# samd5x5.net
KiCad netlist of a schematic drawn in EAGLE
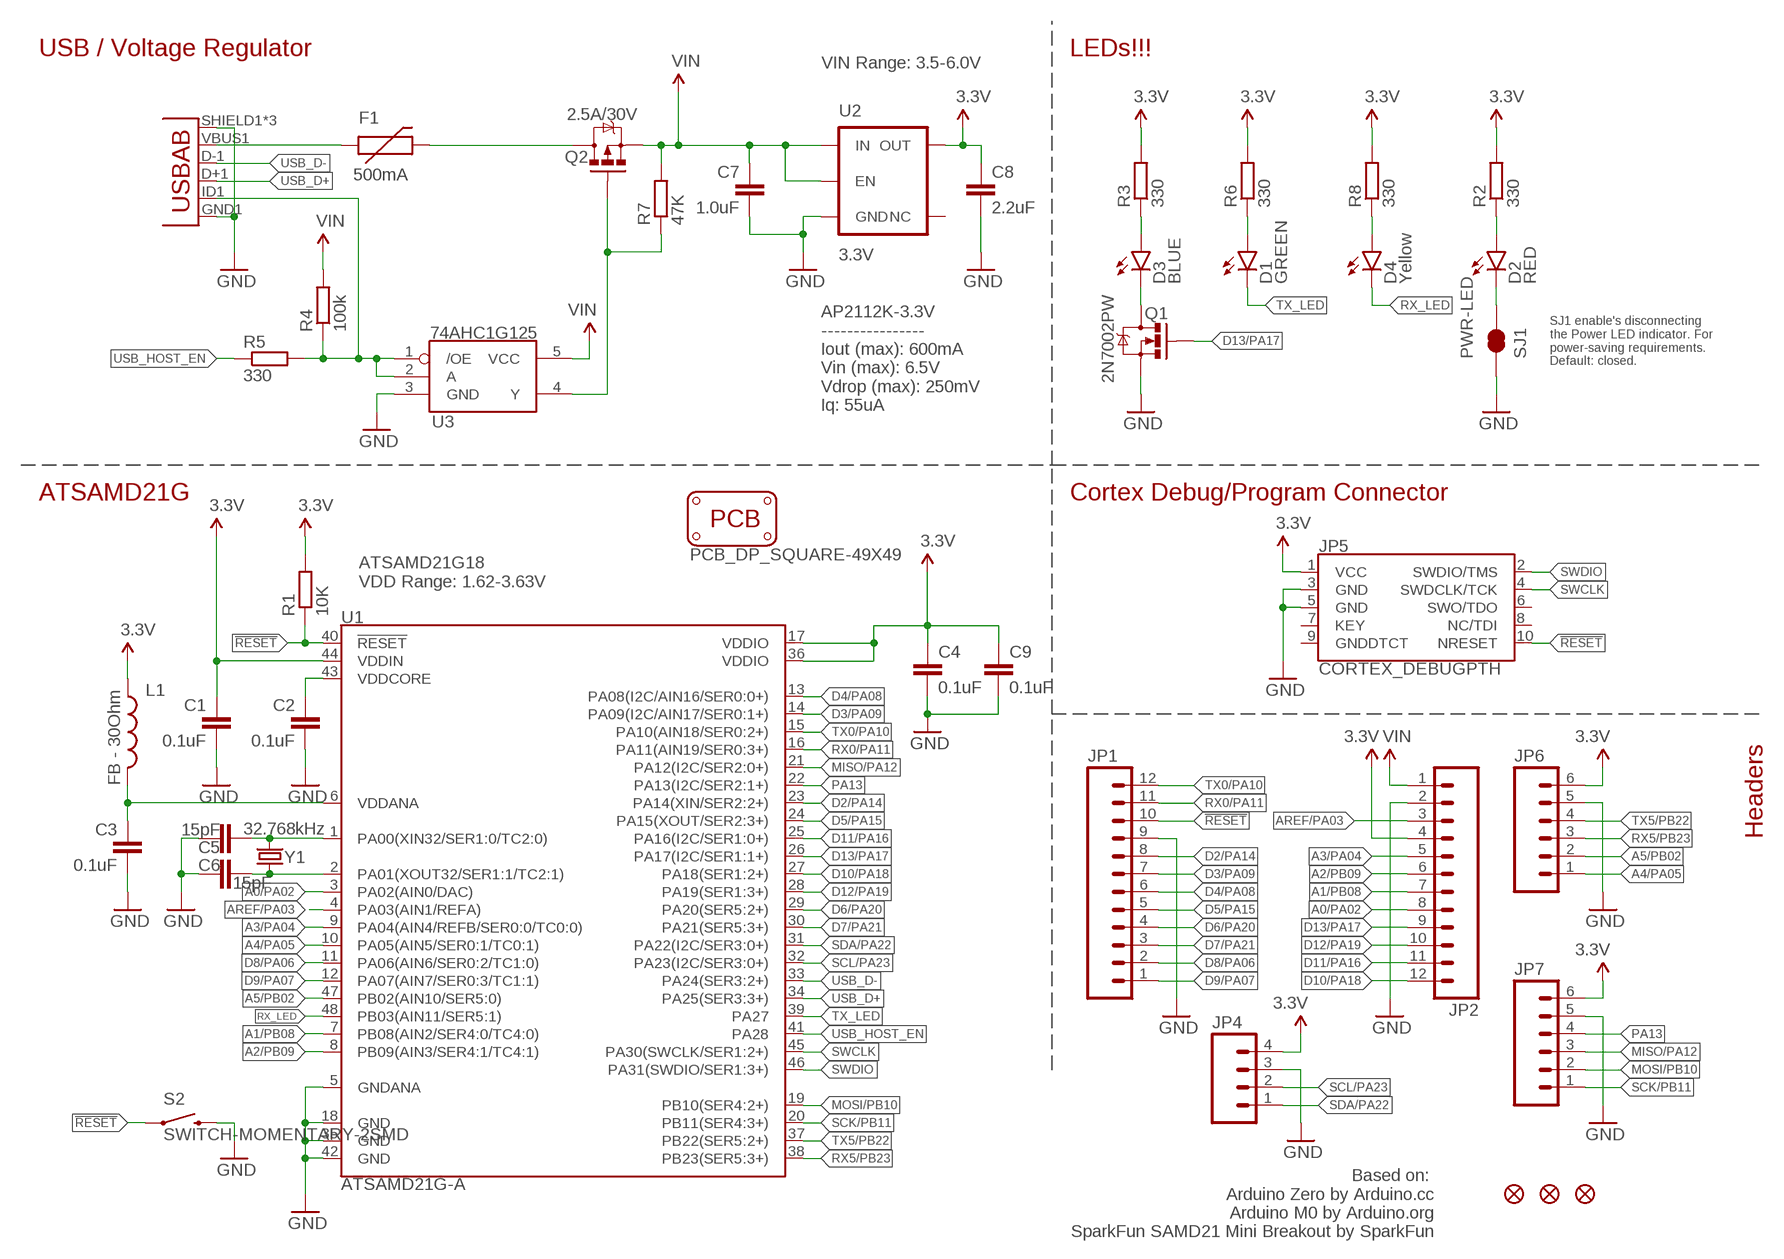
[diagram p0: schematic, sheet 1]

(export (version "E")
  (design (tool "Eeschema 10.0.6"))
  (components
    (comp (ref "C1")
      (value "0.1uF")
      (footprint "eagle-import:0402-CAP")
      (libsource (lib "eagle-import") (part "0.1UF-16V(+-10%)(0402)"))
    )
    (comp (ref "C2")
      (value "0.1uF")
      (footprint "eagle-import:0402-CAP")
      (libsource (lib "eagle-import") (part "0.1UF-16V(+-10%)(0402)"))
    )
    (comp (ref "C3")
      (value "0.1uF")
      (footprint "eagle-import:0402-CAP")
      (libsource (lib "eagle-import") (part "0.1UF-16V(+-10%)(0402)"))
    )
    (comp (ref "C4")
      (value "0.1uF")
      (footprint "eagle-import:0402-CAP")
      (libsource (lib "eagle-import") (part "0.1UF-16V(+-10%)(0402)"))
    )
    (comp (ref "C5")
      (value "15pF")
      (footprint "eagle-import:0402-CAP")
      (libsource (lib "eagle-import") (part "15PF-50V(+-5%)(0402)"))
    )
    (comp (ref "C6")
      (value "15pF")
      (footprint "eagle-import:0402-CAP")
      (libsource (lib "eagle-import") (part "15PF-50V(+-5%)(0402)"))
    )
    (comp (ref "C7")
      (value "1.0uF")
      (footprint "eagle-import:C0603K")
      (libsource (lib "eagle-import") (part "C-EUC0603K"))
    )
    (comp (ref "C8")
      (value "2.2uF")
      (footprint "eagle-import:0603-CAP")
      (libsource (lib "eagle-import") (part "2.2UF-10V-20%(0603)"))
    )
    (comp (ref "C9")
      (value "0.1uF")
      (footprint "eagle-import:0402-CAP")
      (libsource (lib "eagle-import") (part "0.1UF-16V(+-10%)(0402)"))
    )
    (comp (ref "D1")
      (value "GREEN")
      (footprint "eagle-import:LED-0603")
      (libsource (lib "eagle-import") (part "LED-GREEN0603"))
    )
    (comp (ref "D2")
      (value "RED")
      (footprint "eagle-import:LED-0603")
      (libsource (lib "eagle-import") (part "LED-RED0603"))
    )
    (comp (ref "D3")
      (value "BLUE")
      (footprint "eagle-import:LED-0603")
      (libsource (lib "eagle-import") (part "LED-BLUE0603"))
    )
    (comp (ref "D4")
      (value "Yellow")
      (footprint "eagle-import:LED-0603")
      (libsource (lib "eagle-import") (part "LED-YELLOW0603"))
    )
    (comp (ref "F1")
      (value "500mA")
      (footprint "eagle-import:PTC-1206")
      (libsource (lib "eagle-import") (part "PTCSMD"))
    )
    (comp (ref "FID1")
      (value "FIDUCIAL1X2")
      (footprint "eagle-import:FIDUCIAL-1X2")
      (libsource (lib "eagle-import") (part "FIDUCIAL1X2"))
    )
    (comp (ref "FID2")
      (value "FIDUCIAL1X2")
      (footprint "eagle-import:FIDUCIAL-1X2")
      (libsource (lib "eagle-import") (part "FIDUCIAL1X2"))
    )
    (comp (ref "FID3")
      (value "FIDUCIAL1X2")
      (footprint "eagle-import:FIDUCIAL-1X2")
      (libsource (lib "eagle-import") (part "FIDUCIAL1X2"))
    )
    (comp (ref "JP1")
      (value "M12NO_SILK")
      (footprint "eagle-import:1X12_NO_SILK")
      (libsource (lib "eagle-import") (part "M12NO_SILK"))
    )
    (comp (ref "JP2")
      (value "M12NO_SILK")
      (footprint "eagle-import:1X12_NO_SILK")
      (libsource (lib "eagle-import") (part "M12NO_SILK"))
    )
    (comp (ref "JP3")
      (value "USB-ABCONN-11794")
      (footprint "eagle-import:USB-AB-MICRO-SMD_V03")
      (libsource (lib "eagle-import") (part "USB-ABCONN-11794"))
    )
    (comp (ref "JP4")
      (value "M041X04_NO_SILK")
      (footprint "eagle-import:1X04_NO_SILK")
      (libsource (lib "eagle-import") (part "M041X04_NO_SILK"))
    )
    (comp (ref "JP5")
      (value "CORTEX_DEBUGPTH")
      (footprint "eagle-import:2X5-PTH-1.27MM")
      (libsource (lib "eagle-import") (part "CORTEX_DEBUGPTH"))
    )
    (comp (ref "JP6")
      (value "M06NO_SILK_FEMALE_PTH")
      (footprint "eagle-import:1X06_NO_SILK")
      (libsource (lib "eagle-import") (part "M06NO_SILK_FEMALE_PTH"))
    )
    (comp (ref "JP7")
      (value "M06NO_SILK_FEMALE_PTH")
      (footprint "eagle-import:1X06_NO_SILK")
      (libsource (lib "eagle-import") (part "M06NO_SILK_FEMALE_PTH"))
    )
    (comp (ref "L1")
      (value "FB - 30Ohm")
      (footprint "eagle-import:0603")
      (libsource (lib "eagle-import") (part "INDUCTOR0603"))
    )
    (comp (ref "PCB1")
      (value "PCB_DP_SQUARE-49X49")
      (footprint "eagle-import:DP4949V1")
      (libsource (lib "eagle-import") (part "PCB_DP_SQUARE-49X49"))
    )
    (comp (ref "Q1")
      (value "2N7002PW")
      (footprint "eagle-import:SOT323")
      (libsource (lib "eagle-import") (part "MOSFET-NCHANNEL2N7002PW"))
    )
    (comp (ref "Q2")
      (value "2.5A/30V")
      (footprint "eagle-import:SOT23-3")
      (libsource (lib "eagle-import") (part "MOSFET-PCHANNELDMG2307L"))
    )
    (comp (ref "R1")
      (value "10K")
      (footprint "eagle-import:R0402")
      (libsource (lib "eagle-import") (part "R-EU_R0402"))
    )
    (comp (ref "R2")
      (value "330")
      (footprint "eagle-import:R0402")
      (libsource (lib "eagle-import") (part "R-EU_R0402"))
    )
    (comp (ref "R3")
      (value "330")
      (footprint "eagle-import:R0402")
      (libsource (lib "eagle-import") (part "R-EU_R0402"))
    )
    (comp (ref "R4")
      (value "100k")
      (footprint "eagle-import:R0402")
      (libsource (lib "eagle-import") (part "R-EU_R0402"))
    )
    (comp (ref "R5")
      (value "330")
      (footprint "eagle-import:R0402")
      (libsource (lib "eagle-import") (part "R-EU_R0402"))
    )
    (comp (ref "R6")
      (value "330")
      (footprint "eagle-import:R0402")
      (libsource (lib "eagle-import") (part "R-EU_R0402"))
    )
    (comp (ref "R7")
      (value "47K")
      (footprint "eagle-import:R0402")
      (libsource (lib "eagle-import") (part "R-EU_R0402"))
    )
    (comp (ref "R8")
      (value "330")
      (footprint "eagle-import:R0402")
      (libsource (lib "eagle-import") (part "R-EU_R0402"))
    )
    (comp (ref "S2")
      (value "SWITCH-MOMENTARY-2SMD")
      (footprint "eagle-import:TACTILE-SWITCH-SMD")
      (libsource (lib "eagle-import") (part "SWITCH-MOMENTARY-2SMD"))
    )
    (comp (ref "SJ1")
      (value "PWR-LED")
      (footprint "eagle-import:PAD-JUMPER-2-NC_BY_TRACE_NO_SILK")
      (libsource (lib "eagle-import") (part "JUMPER-PAD-2-NC_BY_TRACENO_SILK"))
    )
    (comp (ref "U1")
      (value "ATSAMD21G-A")
      (footprint "eagle-import:TQFP-48")
      (libsource (lib "eagle-import") (part "ATSAMD21G-A"))
    )
    (comp (ref "U2")
      (value "3.3V")
      (footprint "eagle-import:SOT23-5")
      (libsource (lib "eagle-import") (part "V_REG_AP2112K-3.3V"))
    )
    (comp (ref "U3")
      (value "74AHC1G125")
      (footprint "eagle-import:SOT23-5")
      (libsource (lib "eagle-import") (part "74AHC1G125"))
    )
    (comp (ref "Y1")
      (value "32.768kHz")
      (footprint "eagle-import:CRYSTAL-SMD-3.2X1.5MM")
      (libsource (lib "eagle-import") (part "CRYSTAL3.2X1.5MM"))
    )
  )
  (nets
    (net (code "1") (name "/~{RESET}") (class "Default")
      (node (ref "JP1") (pin "10") (pinfunction "10_10") (pintype "passive"))
      (node (ref "JP5") (pin "10") (pinfunction "NRESET_10") (pintype "bidirectional"))
      (node (ref "R1") (pin "1") (pinfunction "1_1") (pintype "passive"))
      (node (ref "S2") (pin "1") (pinfunction "1_1") (pintype "passive"))
      (node (ref "U1") (pin "40") (pinfunction "~{RESET}_40") (pintype "bidirectional"))
    )
    (net (code "2") (name "3.3V") (class "Default")
      (node (ref "C1") (pin "1") (pinfunction "1_1") (pintype "passive"))
      (node (ref "C4") (pin "1") (pinfunction "1_1") (pintype "passive"))
      (node (ref "C8") (pin "1") (pinfunction "1_1") (pintype "passive"))
      (node (ref "C9") (pin "1") (pinfunction "1_1") (pintype "passive"))
      (node (ref "JP2") (pin "4") (pinfunction "4_4") (pintype "passive"))
      (node (ref "JP4") (pin "4") (pinfunction "4_4") (pintype "passive"))
      (node (ref "JP5") (pin "1") (pinfunction "VCC_1") (pintype "bidirectional"))
      (node (ref "JP6") (pin "6") (pinfunction "6_6") (pintype "passive"))
      (node (ref "JP7") (pin "6") (pinfunction "6_6") (pintype "passive"))
      (node (ref "L1") (pin "1") (pinfunction "1_1") (pintype "passive"))
      (node (ref "R1") (pin "2") (pinfunction "2_2") (pintype "passive"))
      (node (ref "R2") (pin "2") (pinfunction "2_2") (pintype "passive"))
      (node (ref "R3") (pin "2") (pinfunction "2_2") (pintype "passive"))
      (node (ref "R6") (pin "2") (pinfunction "2_2") (pintype "passive"))
      (node (ref "R8") (pin "2") (pinfunction "2_2") (pintype "passive"))
      (node (ref "U1") (pin "17") (pinfunction "VDDIO_17") (pintype "bidirectional"))
      (node (ref "U1") (pin "36") (pinfunction "VDDIO_36") (pintype "bidirectional"))
      (node (ref "U1") (pin "44") (pinfunction "VDDIN_44") (pintype "bidirectional"))
      (node (ref "U2") (pin "5") (pinfunction "OUT_5") (pintype "passive"))
    )
    (net (code "3") (name "A0{slash}PA02") (class "Default")
      (node (ref "JP2") (pin "8") (pinfunction "8_8") (pintype "passive"))
      (node (ref "U1") (pin "3") (pinfunction "PA02(AIN0/DAC)_3") (pintype "bidirectional"))
    )
    (net (code "4") (name "A1{slash}PB08") (class "Default")
      (node (ref "JP2") (pin "7") (pinfunction "7_7") (pintype "passive"))
      (node (ref "U1") (pin "7") (pinfunction "PB08(AIN2/SER4:0/TC4:0)_7") (pintype "bidirectional"))
    )
    (net (code "5") (name "A2{slash}PB09") (class "Default")
      (node (ref "JP2") (pin "6") (pinfunction "6_6") (pintype "passive"))
      (node (ref "U1") (pin "8") (pinfunction "PB09(AIN3/SER4:1/TC4:1)_8") (pintype "bidirectional"))
    )
    (net (code "6") (name "A3{slash}PA04") (class "Default")
      (node (ref "JP2") (pin "5") (pinfunction "5_5") (pintype "passive"))
      (node (ref "U1") (pin "9") (pinfunction "PA04(AIN4/REFB/SER0:0/TC0:0)_9") (pintype "bidirectional"))
    )
    (net (code "7") (name "A4{slash}PA05") (class "Default")
      (node (ref "JP6") (pin "1") (pinfunction "1_1") (pintype "passive"))
      (node (ref "U1") (pin "10") (pinfunction "PA05(AIN5/SER0:1/TC0:1)_10") (pintype "bidirectional"))
    )
    (net (code "8") (name "A5{slash}PB02") (class "Default")
      (node (ref "JP6") (pin "2") (pinfunction "2_2") (pintype "passive"))
      (node (ref "U1") (pin "47") (pinfunction "PB02(AIN10/SER5:0)_47") (pintype "bidirectional"))
    )
    (net (code "9") (name "AREF{slash}PA03") (class "Default")
      (node (ref "JP2") (pin "3") (pinfunction "3_3") (pintype "passive"))
      (node (ref "U1") (pin "4") (pinfunction "PA03(AIN1/REFA)_4") (pintype "bidirectional"))
    )
    (net (code "10") (name "D2{slash}PA14") (class "Default")
      (node (ref "JP1") (pin "8") (pinfunction "8_8") (pintype "passive"))
      (node (ref "U1") (pin "23") (pinfunction "PA14(XIN/SER2:2+)_23") (pintype "bidirectional"))
    )
    (net (code "11") (name "D3{slash}PA09") (class "Default")
      (node (ref "JP1") (pin "7") (pinfunction "7_7") (pintype "passive"))
      (node (ref "U1") (pin "14") (pinfunction "PA09(I2C/AIN17/SER0:1+)_14") (pintype "bidirectional"))
    )
    (net (code "12") (name "D4{slash}PA08") (class "Default")
      (node (ref "JP1") (pin "6") (pinfunction "6_6") (pintype "passive"))
      (node (ref "U1") (pin "13") (pinfunction "PA08(I2C/AIN16/SER0:0+)_13") (pintype "bidirectional"))
    )
    (net (code "13") (name "D5{slash}PA15") (class "Default")
      (node (ref "JP1") (pin "5") (pinfunction "5_5") (pintype "passive"))
      (node (ref "U1") (pin "24") (pinfunction "PA15(XOUT/SER2:3+)_24") (pintype "bidirectional"))
    )
    (net (code "14") (name "D6{slash}PA20") (class "Default")
      (node (ref "JP1") (pin "4") (pinfunction "4_4") (pintype "passive"))
      (node (ref "U1") (pin "29") (pinfunction "PA20(SER5:2+)_29") (pintype "bidirectional"))
    )
    (net (code "15") (name "D7{slash}PA21") (class "Default")
      (node (ref "JP1") (pin "3") (pinfunction "3_3") (pintype "passive"))
      (node (ref "U1") (pin "30") (pinfunction "PA21(SER5:3+)_30") (pintype "bidirectional"))
    )
    (net (code "16") (name "D8{slash}PA06") (class "Default")
      (node (ref "JP1") (pin "2") (pinfunction "2_2") (pintype "passive"))
      (node (ref "U1") (pin "11") (pinfunction "PA06(AIN6/SER0:2/TC1:0)_11") (pintype "bidirectional"))
    )
    (net (code "17") (name "D9{slash}PA07") (class "Default")
      (node (ref "JP1") (pin "1") (pinfunction "1_1") (pintype "passive"))
      (node (ref "U1") (pin "12") (pinfunction "PA07(AIN7/SER0:3/TC1:1)_12") (pintype "bidirectional"))
    )
    (net (code "18") (name "D10{slash}PA18") (class "Default")
      (node (ref "JP2") (pin "12") (pinfunction "12_12") (pintype "passive"))
      (node (ref "U1") (pin "27") (pinfunction "PA18(SER1:2+)_27") (pintype "bidirectional"))
    )
    (net (code "19") (name "D11{slash}PA16") (class "Default")
      (node (ref "JP2") (pin "11") (pinfunction "11_11") (pintype "passive"))
      (node (ref "U1") (pin "25") (pinfunction "PA16(I2C/SER1:0+)_25") (pintype "bidirectional"))
    )
    (net (code "20") (name "D12{slash}PA19") (class "Default")
      (node (ref "JP2") (pin "10") (pinfunction "10_10") (pintype "passive"))
      (node (ref "U1") (pin "28") (pinfunction "PA19(SER1:3+)_28") (pintype "bidirectional"))
    )
    (net (code "21") (name "D13{slash}PA17") (class "Default")
      (node (ref "JP2") (pin "9") (pinfunction "9_9") (pintype "passive"))
      (node (ref "Q1") (pin "1") (pinfunction "G_1") (pintype "passive"))
      (node (ref "U1") (pin "26") (pinfunction "PA17(I2C/SER1:1+)_26") (pintype "bidirectional"))
    )
    (net (code "22") (name "GND") (class "Default")
      (node (ref "C1") (pin "2") (pinfunction "2_2") (pintype "passive"))
      (node (ref "C2") (pin "2") (pinfunction "2_2") (pintype "passive"))
      (node (ref "C3") (pin "2") (pinfunction "2_2") (pintype "passive"))
      (node (ref "C4") (pin "2") (pinfunction "2_2") (pintype "passive"))
      (node (ref "C5") (pin "1") (pinfunction "1_1") (pintype "passive"))
      (node (ref "C6") (pin "2") (pinfunction "2_2") (pintype "passive"))
      (node (ref "C7") (pin "2") (pinfunction "2_2") (pintype "passive"))
      (node (ref "C8") (pin "2") (pinfunction "2_2") (pintype "passive"))
      (node (ref "C9") (pin "2") (pinfunction "2_2") (pintype "passive"))
      (node (ref "JP1") (pin "9") (pinfunction "9_9") (pintype "passive"))
      (node (ref "JP2") (pin "2") (pinfunction "2_2") (pintype "passive"))
      (node (ref "JP3") (pin "GND1") (pinfunction "GND_GND1") (pintype "bidirectional"))
      (node (ref "JP3") (pin "SHIELD1") (pinfunction "SHIELD_SHIELD1") (pintype "bidirectional"))
      (node (ref "JP3") (pin "SHIELD2") (pinfunction "SHIELD_SHIELD2") (pintype "bidirectional"))
      (node (ref "JP3") (pin "SHIELD3") (pinfunction "SHIELD_SHIELD3") (pintype "bidirectional"))
      (node (ref "JP4") (pin "3") (pinfunction "3_3") (pintype "passive"))
      (node (ref "JP5") (pin "3") (pinfunction "GND_3") (pintype "bidirectional"))
      (node (ref "JP5") (pin "5") (pinfunction "GND_5") (pintype "bidirectional"))
      (node (ref "JP6") (pin "5") (pinfunction "5_5") (pintype "passive"))
      (node (ref "JP7") (pin "5") (pinfunction "5_5") (pintype "passive"))
      (node (ref "Q1") (pin "2") (pinfunction "S_2") (pintype "passive"))
      (node (ref "S2") (pin "3") (pinfunction "2_3") (pintype "passive"))
      (node (ref "SJ1") (pin "1") (pinfunction "1_1") (pintype "passive"))
      (node (ref "U1") (pin "18") (pinfunction "GND_18") (pintype "bidirectional"))
      (node (ref "U1") (pin "35") (pinfunction "GND_35") (pintype "bidirectional"))
      (node (ref "U1") (pin "42") (pinfunction "GND_42") (pintype "bidirectional"))
      (node (ref "U1") (pin "5") (pinfunction "GNDANA_5") (pintype "bidirectional"))
      (node (ref "U2") (pin "2") (pinfunction "GND_2") (pintype "input"))
      (node (ref "U3") (pin "3") (pinfunction "GND_3") (pintype "bidirectional"))
    )
    (net (code "23") (name "MISO{slash}PA12") (class "Default")
      (node (ref "JP7") (pin "3") (pinfunction "3_3") (pintype "passive"))
      (node (ref "U1") (pin "21") (pinfunction "PA12(I2C/SER2:0+)_21") (pintype "bidirectional"))
    )
    (net (code "24") (name "MOSI{slash}PB10") (class "Default")
      (node (ref "JP7") (pin "2") (pinfunction "2_2") (pintype "passive"))
      (node (ref "U1") (pin "19") (pinfunction "PB10(SER4:2+)_19") (pintype "bidirectional"))
    )
    (net (code "25") (name "Net-(D1-PadA)") (class "Default")
      (node (ref "D1") (pin "A") (pinfunction "A_A") (pintype "passive"))
      (node (ref "R6") (pin "1") (pinfunction "1_1") (pintype "passive"))
    )
    (net (code "26") (name "Net-(D2-PadA)") (class "Default")
      (node (ref "D2") (pin "A") (pinfunction "A_A") (pintype "passive"))
      (node (ref "R2") (pin "1") (pinfunction "1_1") (pintype "passive"))
    )
    (net (code "27") (name "Net-(D2-PadC)") (class "Default")
      (node (ref "D2") (pin "C") (pinfunction "C_C") (pintype "passive"))
      (node (ref "SJ1") (pin "2") (pinfunction "2_2") (pintype "passive"))
    )
    (net (code "28") (name "Net-(D3-PadA)") (class "Default")
      (node (ref "D3") (pin "A") (pinfunction "A_A") (pintype "passive"))
      (node (ref "R3") (pin "1") (pinfunction "1_1") (pintype "passive"))
    )
    (net (code "29") (name "Net-(D4-PadA)") (class "Default")
      (node (ref "D4") (pin "A") (pinfunction "A_A") (pintype "passive"))
      (node (ref "R8") (pin "1") (pinfunction "1_1") (pintype "passive"))
    )
    (net (code "30") (name "Net-(JP3-USBID)") (class "Default")
      (node (ref "JP3") (pin "ID1") (pinfunction "USBID_ID1") (pintype "bidirectional"))
      (node (ref "R4") (pin "1") (pinfunction "1_1") (pintype "passive"))
      (node (ref "R5") (pin "2") (pinfunction "2_2") (pintype "passive"))
      (node (ref "U3") (pin "1") (pinfunction "/OE_1") (pintype "bidirectional"))
      (node (ref "U3") (pin "2") (pinfunction "A_2") (pintype "bidirectional"))
    )
    (net (code "31") (name "Net-(JP3-VBUS)") (class "Default")
      (node (ref "F1") (pin "1") (pinfunction "1_1") (pintype "bidirectional"))
      (node (ref "JP3") (pin "VBUS1") (pinfunction "VBUS_VBUS1") (pintype "bidirectional"))
    )
    (net (code "32") (name "Net-(Q1-D)") (class "Default")
      (node (ref "D3") (pin "C") (pinfunction "C_C") (pintype "passive"))
      (node (ref "Q1") (pin "3") (pinfunction "D_3") (pintype "passive"))
    )
    (net (code "33") (name "Net-(Q2-D)") (class "Default")
      (node (ref "F1") (pin "2") (pinfunction "2_2") (pintype "bidirectional"))
      (node (ref "Q2") (pin "3") (pinfunction "D_3") (pintype "passive"))
    )
    (net (code "34") (name "Net-(Q2-G)") (class "Default")
      (node (ref "Q2") (pin "1") (pinfunction "G_1") (pintype "passive"))
      (node (ref "R7") (pin "1") (pinfunction "1_1") (pintype "passive"))
      (node (ref "U3") (pin "4") (pinfunction "Y_4") (pintype "bidirectional"))
    )
    (net (code "35") (name "Net-(U1-PA00(XIN32{slash}SER1:0{slash}TC2:0))") (class "Default")
      (node (ref "C5") (pin "2") (pinfunction "2_2") (pintype "passive"))
      (node (ref "U1") (pin "1") (pinfunction "PA00(XIN32/SER1:0/TC2:0)_1") (pintype "bidirectional"))
      (node (ref "Y1") (pin "P$2") (pinfunction "2_P$2") (pintype "passive"))
    )
    (net (code "36") (name "Net-(U1-PA01(XOUT32{slash}SER1:1{slash}TC2:1))") (class "Default")
      (node (ref "C6") (pin "1") (pinfunction "1_1") (pintype "passive"))
      (node (ref "U1") (pin "2") (pinfunction "PA01(XOUT32/SER1:1/TC2:1)_2") (pintype "bidirectional"))
      (node (ref "Y1") (pin "P$1") (pinfunction "1_P$1") (pintype "passive"))
    )
    (net (code "37") (name "Net-(U1-VDDANA)") (class "Default")
      (node (ref "C3") (pin "1") (pinfunction "1_1") (pintype "passive"))
      (node (ref "L1") (pin "2") (pinfunction "2_2") (pintype "passive"))
      (node (ref "U1") (pin "6") (pinfunction "VDDANA_6") (pintype "bidirectional"))
    )
    (net (code "38") (name "Net-(U1-VDDCORE)") (class "Default")
      (node (ref "C2") (pin "1") (pinfunction "1_1") (pintype "passive"))
      (node (ref "U1") (pin "43") (pinfunction "VDDCORE_43") (pintype "bidirectional"))
    )
    (net (code "39") (name "PA13") (class "Default")
      (node (ref "JP7") (pin "4") (pinfunction "4_4") (pintype "passive"))
      (node (ref "U1") (pin "22") (pinfunction "PA13(I2C/SER2:1+)_22") (pintype "bidirectional"))
    )
    (net (code "40") (name "RX0{slash}PA11") (class "Default")
      (node (ref "JP1") (pin "11") (pinfunction "11_11") (pintype "passive"))
      (node (ref "U1") (pin "16") (pinfunction "PA11(AIN19/SER0:3+)_16") (pintype "bidirectional"))
    )
    (net (code "41") (name "RX5{slash}PB23") (class "Default")
      (node (ref "JP6") (pin "3") (pinfunction "3_3") (pintype "passive"))
      (node (ref "U1") (pin "38") (pinfunction "PB23(SER5:3+)_38") (pintype "bidirectional"))
    )
    (net (code "42") (name "RX_LED") (class "Default")
      (node (ref "D4") (pin "C") (pinfunction "C_C") (pintype "passive"))
      (node (ref "U1") (pin "48") (pinfunction "PB03(AIN11/SER5:1)_48") (pintype "bidirectional"))
    )
    (net (code "43") (name "SCK{slash}PB11") (class "Default")
      (node (ref "JP7") (pin "1") (pinfunction "1_1") (pintype "passive"))
      (node (ref "U1") (pin "20") (pinfunction "PB11(SER4:3+)_20") (pintype "bidirectional"))
    )
    (net (code "44") (name "SCL{slash}PA23") (class "Default")
      (node (ref "JP4") (pin "2") (pinfunction "2_2") (pintype "passive"))
      (node (ref "U1") (pin "32") (pinfunction "PA23(I2C/SER3:0+)_32") (pintype "bidirectional"))
    )
    (net (code "45") (name "SDA{slash}PA22") (class "Default")
      (node (ref "JP4") (pin "1") (pinfunction "1_1") (pintype "passive"))
      (node (ref "U1") (pin "31") (pinfunction "PA22(I2C/SER3:0+)_31") (pintype "bidirectional"))
    )
    (net (code "46") (name "SWCLK") (class "Default")
      (node (ref "JP5") (pin "4") (pinfunction "SWDCLK/TCK_4") (pintype "bidirectional"))
      (node (ref "U1") (pin "45") (pinfunction "PA30(SWCLK/SER1:2+)_45") (pintype "bidirectional"))
    )
    (net (code "47") (name "SWDIO") (class "Default")
      (node (ref "JP5") (pin "2") (pinfunction "SWDIO/TMS_2") (pintype "bidirectional"))
      (node (ref "U1") (pin "46") (pinfunction "PA31(SWDIO/SER1:3+)_46") (pintype "bidirectional"))
    )
    (net (code "48") (name "TX0{slash}PA10") (class "Default")
      (node (ref "JP1") (pin "12") (pinfunction "12_12") (pintype "passive"))
      (node (ref "U1") (pin "15") (pinfunction "PA10(AIN18/SER0:2+)_15") (pintype "bidirectional"))
    )
    (net (code "49") (name "TX5{slash}PB22") (class "Default")
      (node (ref "JP6") (pin "4") (pinfunction "4_4") (pintype "passive"))
      (node (ref "U1") (pin "37") (pinfunction "PB22(SER5:2+)_37") (pintype "bidirectional"))
    )
    (net (code "50") (name "TX_LED") (class "Default")
      (node (ref "D1") (pin "C") (pinfunction "C_C") (pintype "passive"))
      (node (ref "U1") (pin "39") (pinfunction "PA27_39") (pintype "bidirectional"))
    )
    (net (code "51") (name "USB_D+") (class "Default")
      (node (ref "JP3") (pin "D+1") (pinfunction "D+_D+1") (pintype "bidirectional"))
      (node (ref "U1") (pin "34") (pinfunction "PA25(SER3:3+)_34") (pintype "bidirectional"))
    )
    (net (code "52") (name "USB_D-") (class "Default")
      (node (ref "JP3") (pin "D-1") (pinfunction "D-_D-1") (pintype "bidirectional"))
      (node (ref "U1") (pin "33") (pinfunction "PA24(SER3:2+)_33") (pintype "bidirectional"))
    )
    (net (code "53") (name "USB_HOST_EN") (class "Default")
      (node (ref "R5") (pin "1") (pinfunction "1_1") (pintype "passive"))
      (node (ref "U1") (pin "41") (pinfunction "PA28_41") (pintype "bidirectional"))
    )
    (net (code "54") (name "VIN") (class "Default")
      (node (ref "C7") (pin "1") (pinfunction "1_1") (pintype "passive"))
      (node (ref "JP2") (pin "1") (pinfunction "1_1") (pintype "passive"))
      (node (ref "Q2") (pin "2") (pinfunction "S_2") (pintype "passive"))
      (node (ref "R4") (pin "2") (pinfunction "2_2") (pintype "passive"))
      (node (ref "R7") (pin "2") (pinfunction "2_2") (pintype "passive"))
      (node (ref "U2") (pin "1") (pinfunction "IN_1") (pintype "input"))
      (node (ref "U2") (pin "3") (pinfunction "EN_3") (pintype "input"))
      (node (ref "U3") (pin "5") (pinfunction "VCC_5") (pintype "bidirectional"))
    )
    (net (code "55") (name "unconnected-(JP5-GNDDTCT-Pad9)") (class "Default")
      (node (ref "JP5") (pin "9") (pinfunction "GNDDTCT_9") (pintype "bidirectional"))
    )
    (net (code "56") (name "unconnected-(JP5-KEY-Pad7)") (class "Default")
      (node (ref "JP5") (pin "7") (pinfunction "KEY_7") (pintype "bidirectional"))
    )
    (net (code "57") (name "unconnected-(JP5-NC{slash}TDI-Pad8)") (class "Default")
      (node (ref "JP5") (pin "8") (pinfunction "NC/TDI_8") (pintype "bidirectional"))
    )
    (net (code "58") (name "unconnected-(JP5-SWO{slash}TDO-Pad6)") (class "Default")
      (node (ref "JP5") (pin "6") (pinfunction "SWO/TDO_6") (pintype "bidirectional"))
    )
    (net (code "59") (name "unconnected-(U2-NC-Pad4)") (class "Default")
      (node (ref "U2") (pin "4") (pinfunction "NC_4") (pintype "input"))
    )
  )
)
